# RobotCtrl_V2_Mother-board_Func.net
KiCad netlist of a schematic drawn in Altium Designer
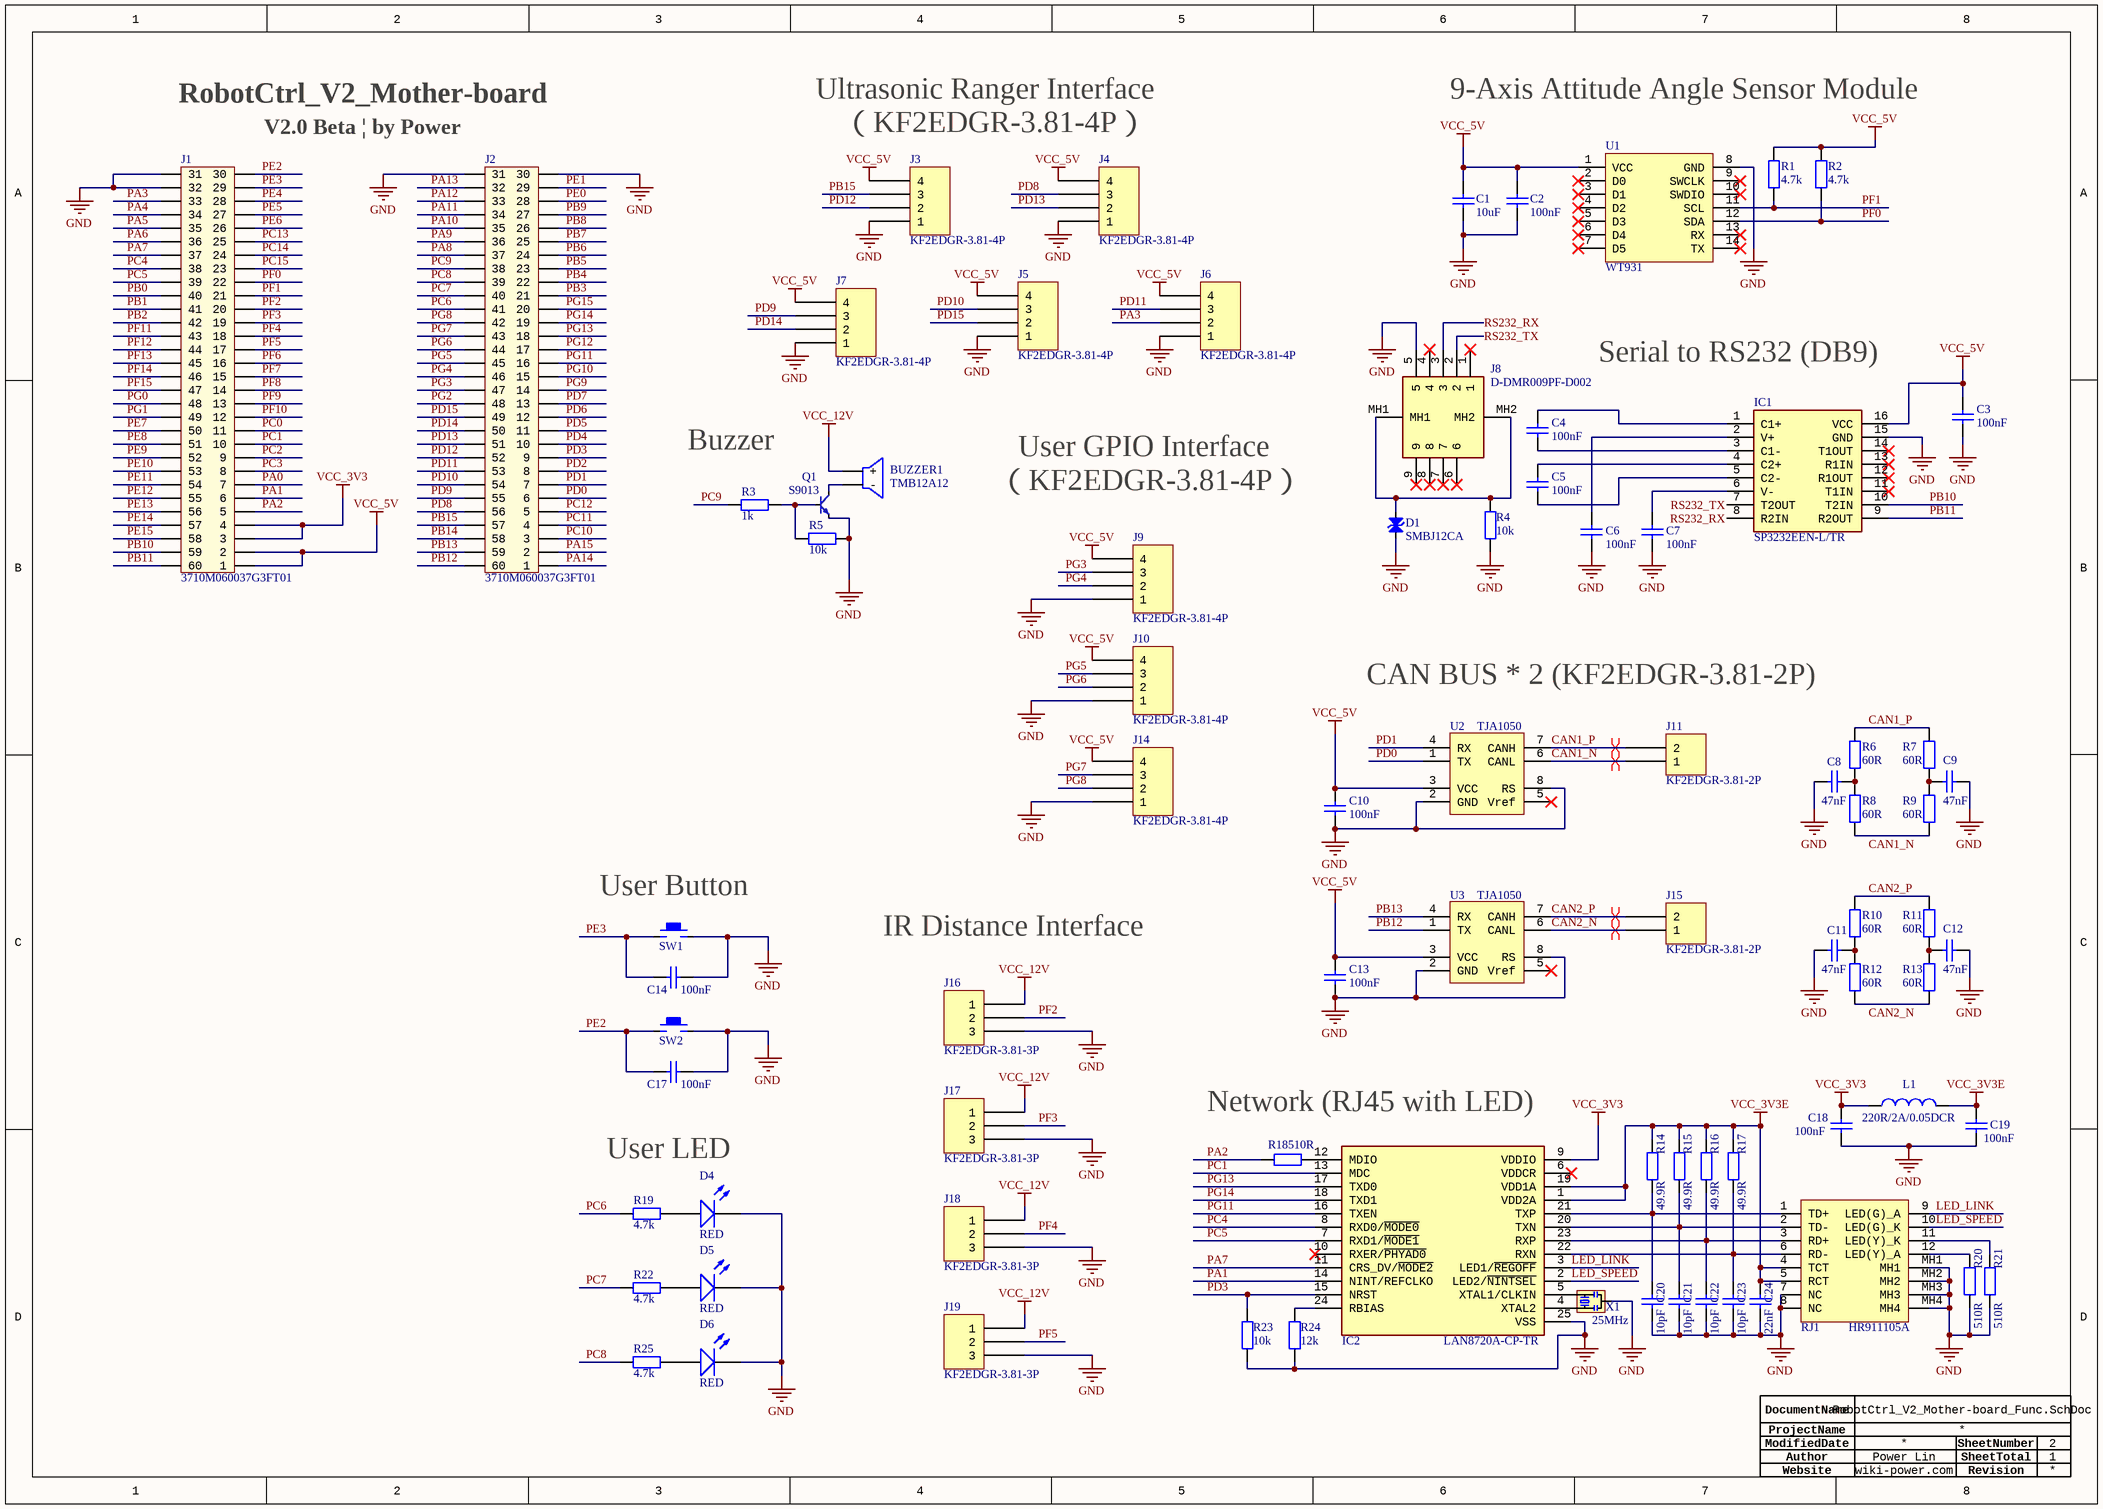
[diagram p0: RobotCtrl_V2_Mother-board_Func.SchDoc]

(export (version "E")
  (design (tool "Eeschema 10.0.6"))
  (components
    (comp (ref "BUZZER1")
      (value "TMB12A12")
      (footprint "DIP,P=7.6mm")
      (description "TMB12A12 有源蜂鸣器")
      (libsource (lib "Power_Lib_Altium") (part "BUZZER"))
    )
    (comp (ref "C1")
      (value "10uF")
      (footprint "CAP-0603")
      (description "贴片电容")
      (libsource (lib "Power_Lib_Altium") (part "CAP"))
    )
    (comp (ref "C2")
      (value "100nF")
      (footprint "CAP-0603")
      (description "贴片电容")
      (libsource (lib "Power_Lib_Altium") (part "CAP"))
    )
    (comp (ref "C3")
      (value "100nF")
      (footprint "CAP-0603")
      (description "贴片电容")
      (libsource (lib "Power_Lib_Altium") (part "CAP"))
    )
    (comp (ref "C4")
      (value "100nF")
      (footprint "CAP-0603")
      (description "贴片电容")
      (libsource (lib "Power_Lib_Altium") (part "CAP"))
    )
    (comp (ref "C5")
      (value "100nF")
      (footprint "CAP-0603")
      (description "贴片电容")
      (libsource (lib "Power_Lib_Altium") (part "CAP"))
    )
    (comp (ref "C6")
      (value "100nF")
      (footprint "CAP-0603")
      (description "贴片电容")
      (libsource (lib "Power_Lib_Altium") (part "CAP"))
    )
    (comp (ref "C7")
      (value "100nF")
      (footprint "CAP-0603")
      (description "贴片电容")
      (libsource (lib "Power_Lib_Altium") (part "CAP"))
    )
    (comp (ref "C8")
      (value "47nF")
      (footprint "CAP-0603")
      (description "贴片电容")
      (libsource (lib "Power_Lib_Altium") (part "CAP"))
    )
    (comp (ref "C9")
      (value "47nF")
      (footprint "CAP-0603")
      (description "贴片电容")
      (libsource (lib "Power_Lib_Altium") (part "CAP"))
    )
    (comp (ref "C10")
      (value "100nF")
      (footprint "CAP-0603")
      (description "贴片电容")
      (libsource (lib "Power_Lib_Altium") (part "CAP"))
    )
    (comp (ref "C11")
      (value "47nF")
      (footprint "CAP-0603")
      (description "贴片电容")
      (libsource (lib "Power_Lib_Altium") (part "CAP"))
    )
    (comp (ref "C12")
      (value "47nF")
      (footprint "CAP-0603")
      (description "贴片电容")
      (libsource (lib "Power_Lib_Altium") (part "CAP"))
    )
    (comp (ref "C13")
      (value "100nF")
      (footprint "CAP-0603")
      (description "贴片电容")
      (libsource (lib "Power_Lib_Altium") (part "CAP"))
    )
    (comp (ref "C14")
      (value "100nF")
      (footprint "CAP-0603")
      (description "贴片电容")
      (libsource (lib "Power_Lib_Altium") (part "CAP"))
    )
    (comp (ref "C17")
      (value "100nF")
      (footprint "CAP-0603")
      (description "贴片电容")
      (libsource (lib "Power_Lib_Altium") (part "CAP"))
    )
    (comp (ref "C18")
      (value "100nF")
      (footprint "CAP-0603")
      (description "贴片电容")
      (libsource (lib "Power_Lib_Altium") (part "CAP"))
    )
    (comp (ref "C19")
      (value "100nF")
      (footprint "CAP-0603")
      (description "贴片电容")
      (libsource (lib "Power_Lib_Altium") (part "CAP"))
    )
    (comp (ref "C20")
      (value "10pF")
      (footprint "CAP-0603")
      (description "贴片电容")
      (libsource (lib "Power_Lib_Altium") (part "CAP"))
    )
    (comp (ref "C21")
      (value "10pF")
      (footprint "CAP-0603")
      (description "贴片电容")
      (libsource (lib "Power_Lib_Altium") (part "CAP"))
    )
    (comp (ref "C22")
      (value "10pF")
      (footprint "CAP-0603")
      (description "贴片电容")
      (libsource (lib "Power_Lib_Altium") (part "CAP"))
    )
    (comp (ref "C23")
      (value "10pF")
      (footprint "CAP-0603")
      (description "贴片电容")
      (libsource (lib "Power_Lib_Altium") (part "CAP"))
    )
    (comp (ref "C24")
      (value "22nF")
      (footprint "CAP-0603")
      (description "贴片电容")
      (libsource (lib "Power_Lib_Altium") (part "CAP"))
    )
    (comp (ref "D1")
      (value "SMBJ12CA")
      (footprint "DO-214AA/SMB")
      (libsource (lib "Power_Lib_Altium") (part "TVS_C"))
    )
    (comp (ref "D4")
      (value "RED")
      (footprint "LED-0603")
      (description "发光二极管")
      (libsource (lib "Power_Lib_Altium") (part "LED"))
    )
    (comp (ref "D5")
      (value "RED")
      (footprint "LED-0603")
      (description "发光二极管")
      (libsource (lib "Power_Lib_Altium") (part "LED"))
    )
    (comp (ref "D6")
      (value "RED")
      (footprint "LED-0603")
      (description "发光二极管")
      (libsource (lib "Power_Lib_Altium") (part "LED"))
    )
    (comp (ref "IC1")
      (value "SP3232EEN-L/TR")
      (footprint "SOIC-16_150mil")
      (description "RS232 芯片")
      (fields (field (name "MOUSER PART NUMBER") "701-SP3232EEN-L/TR"))
      (libsource (lib "Power_Lib_Altium") (part "SP3232EEN"))
    )
    (comp (ref "IC2")
      (value "LAN8720A-CP-TR")
      (footprint "QFN-24-4x4")
      (description "Integrated Circuit")
      (fields (field (name "MOUSER PART NUMBER") "886-LAN8720A-CP-TR"))
      (libsource (lib "Power_Lib_Altium") (part "LAN8720A-CP-TR"))
    )
    (comp (ref "J1")
      (value "3710M060037G3FT01")
      (footprint "3710M060037G3FT01")
      (description "B2B Connector")
      (libsource (lib "Power_Lib_Altium") (part "3710M/F"))
    )
    (comp (ref "J2")
      (value "3710M060037G3FT01")
      (footprint "3710M060037G3FT01")
      (description "B2B Connector")
      (libsource (lib "Power_Lib_Altium") (part "3710M/F"))
    )
    (comp (ref "J3")
      (value "KF2EDGR-3.81-4P")
      (footprint "FCI 06-381-4PIN")
      (description "TERM BLOCK HDR 4POS 90DEG 3.81MM")
      (fields (field (name "PART NUMBER") "OQ0432510000G") (field (name "MANUFACTURER") "Amphenol Anytek"))
      (libsource (lib "Power_Lib_Altium") (part "KF2EDGR-3.81-4P"))
    )
    (comp (ref "J4")
      (value "KF2EDGR-3.81-4P")
      (footprint "FCI 06-381-4PIN")
      (description "TERM BLOCK HDR 4POS 90DEG 3.81MM")
      (fields (field (name "PART NUMBER") "OQ0432510000G") (field (name "MANUFACTURER") "Amphenol Anytek"))
      (libsource (lib "Power_Lib_Altium") (part "KF2EDGR-3.81-4P"))
    )
    (comp (ref "J5")
      (value "KF2EDGR-3.81-4P")
      (footprint "FCI 06-381-4PIN")
      (description "TERM BLOCK HDR 4POS 90DEG 3.81MM")
      (fields (field (name "PART NUMBER") "OQ0432510000G") (field (name "MANUFACTURER") "Amphenol Anytek"))
      (libsource (lib "Power_Lib_Altium") (part "KF2EDGR-3.81-4P"))
    )
    (comp (ref "J6")
      (value "KF2EDGR-3.81-4P")
      (footprint "FCI 06-381-4PIN")
      (description "TERM BLOCK HDR 4POS 90DEG 3.81MM")
      (fields (field (name "PART NUMBER") "OQ0432510000G") (field (name "MANUFACTURER") "Amphenol Anytek"))
      (libsource (lib "Power_Lib_Altium") (part "KF2EDGR-3.81-4P"))
    )
    (comp (ref "J7")
      (value "KF2EDGR-3.81-4P")
      (footprint "FCI 06-381-4PIN")
      (description "TERM BLOCK HDR 4POS 90DEG 3.81MM")
      (fields (field (name "PART NUMBER") "OQ0432510000G") (field (name "MANUFACTURER") "Amphenol Anytek"))
      (libsource (lib "Power_Lib_Altium") (part "KF2EDGR-3.81-4P"))
    )
    (comp (ref "J8")
      (value "D-DMR009PF-D002")
      (footprint "Through Hole,P=2.77mm")
      (description "D-Sub 连接器")
      (fields
        (field (name "MANUFACTURER_PART_NUMBER") "5747844-5")
        (field (name "MOUSER PART NUMBER") "571-5747844-5")
      )
      (libsource (lib "Power_Lib_Altium") (part "DB9"))
    )
    (comp (ref "J9")
      (value "KF2EDGR-3.81-4P")
      (footprint "FCI 06-381-4PIN")
      (description "TERM BLOCK HDR 4POS 90DEG 3.81MM")
      (fields (field (name "PART NUMBER") "OQ0432510000G") (field (name "MANUFACTURER") "Amphenol Anytek"))
      (libsource (lib "Power_Lib_Altium") (part "KF2EDGR-3.81-4P"))
    )
    (comp (ref "J10")
      (value "KF2EDGR-3.81-4P")
      (footprint "FCI 06-381-4PIN")
      (description "TERM BLOCK HDR 4POS 90DEG 3.81MM")
      (fields (field (name "PART NUMBER") "OQ0432510000G") (field (name "MANUFACTURER") "Amphenol Anytek"))
      (libsource (lib "Power_Lib_Altium") (part "KF2EDGR-3.81-4P"))
    )
    (comp (ref "J11")
      (value "KF2EDGR-3.81-2P")
      (footprint "FCI 06-381-2PIN")
      (description "TERM BLOCK HDR 2POS 90DEG 3.81MM")
      (fields (field (name "PART NUMBER") "OQ0232510000G") (field (name "MANUFACTURER") "Amphenol Anytek"))
      (libsource (lib "Power_Lib_Altium") (part "KF2EDGR-3.81-2P"))
    )
    (comp (ref "J14")
      (value "KF2EDGR-3.81-4P")
      (footprint "FCI 06-381-4PIN")
      (description "TERM BLOCK HDR 4POS 90DEG 3.81MM")
      (fields (field (name "PART NUMBER") "OQ0432510000G") (field (name "MANUFACTURER") "Amphenol Anytek"))
      (libsource (lib "Power_Lib_Altium") (part "KF2EDGR-3.81-4P"))
    )
    (comp (ref "J15")
      (value "KF2EDGR-3.81-2P")
      (footprint "FCI 06-381-2PIN")
      (description "TERM BLOCK HDR 2POS 90DEG 3.81MM")
      (fields (field (name "PART NUMBER") "OQ0232510000G") (field (name "MANUFACTURER") "Amphenol Anytek"))
      (libsource (lib "Power_Lib_Altium") (part "KF2EDGR-3.81-2P"))
    )
    (comp (ref "J16")
      (value "KF2EDGR-3.81-3P")
      (footprint "FCI 06-381-3PIN")
      (description "TERM BLOCK HDR 3POS 90DEG 3.81MM")
      (fields (field (name "MANUFACTURER") "Amphenol Anytek") (field (name "PART NUMBER") "OQ0332510000G"))
      (libsource (lib "Power_Lib_Altium") (part "KF2EDGR-3.81-3P"))
    )
    (comp (ref "J17")
      (value "KF2EDGR-3.81-3P")
      (footprint "FCI 06-381-3PIN")
      (description "TERM BLOCK HDR 3POS 90DEG 3.81MM")
      (fields (field (name "MANUFACTURER") "Amphenol Anytek") (field (name "PART NUMBER") "OQ0332510000G"))
      (libsource (lib "Power_Lib_Altium") (part "KF2EDGR-3.81-3P"))
    )
    (comp (ref "J18")
      (value "KF2EDGR-3.81-3P")
      (footprint "FCI 06-381-3PIN")
      (description "TERM BLOCK HDR 3POS 90DEG 3.81MM")
      (fields (field (name "MANUFACTURER") "Amphenol Anytek") (field (name "PART NUMBER") "OQ0332510000G"))
      (libsource (lib "Power_Lib_Altium") (part "KF2EDGR-3.81-3P"))
    )
    (comp (ref "J19")
      (value "KF2EDGR-3.81-3P")
      (footprint "FCI 06-381-3PIN")
      (description "TERM BLOCK HDR 3POS 90DEG 3.81MM")
      (fields (field (name "MANUFACTURER") "Amphenol Anytek") (field (name "PART NUMBER") "OQ0332510000G"))
      (libsource (lib "Power_Lib_Altium") (part "KF2EDGR-3.81-3P"))
    )
    (comp (ref "L1")
      (value "220R/2A/0.05DCR")
      (footprint "L-0603")
      (description "BLM18KG221SN1D")
      (libsource (lib "Power_Lib_Altium") (part "BEAD"))
    )
    (comp (ref "Q1")
      (value "S9013")
      (footprint "SOT-23-3")
      (libsource (lib "Power_Lib_Altium") (part "BJT_NPN"))
    )
    (comp (ref "R1")
      (value "4.7k")
      (footprint "R-0603")
      (description "贴片电阻")
      (libsource (lib "") (part "RES_3"))
    )
    (comp (ref "R2")
      (value "4.7k")
      (footprint "R-0603")
      (description "贴片电阻")
      (libsource (lib "") (part "RES_3"))
    )
    (comp (ref "R3")
      (value "1k")
      (footprint "R-0603")
      (description "贴片电阻")
      (libsource (lib "") (part "RES_2"))
    )
    (comp (ref "R4")
      (value "10k")
      (footprint "R-0603")
      (description "贴片电阻")
      (libsource (lib "") (part "RES_3"))
    )
    (comp (ref "R5")
      (value "10k")
      (footprint "R-0603")
      (description "贴片电阻")
      (libsource (lib "Power_Lib_Altium") (part "RES"))
    )
    (comp (ref "R6")
      (value "60R")
      (footprint "R-0603")
      (description "贴片电阻")
      (libsource (lib "") (part "RES_1"))
    )
    (comp (ref "R7")
      (value "60R")
      (footprint "R-0603")
      (description "贴片电阻")
      (libsource (lib "") (part "RES_3"))
    )
    (comp (ref "R8")
      (value "60R")
      (footprint "R-0603")
      (description "贴片电阻")
      (libsource (lib "") (part "RES_1"))
    )
    (comp (ref "R9")
      (value "60R")
      (footprint "R-0603")
      (description "贴片电阻")
      (libsource (lib "") (part "RES_3"))
    )
    (comp (ref "R10")
      (value "60R")
      (footprint "R-0603")
      (description "贴片电阻")
      (libsource (lib "") (part "RES_1"))
    )
    (comp (ref "R11")
      (value "60R")
      (footprint "R-0603")
      (description "贴片电阻")
      (libsource (lib "") (part "RES_3"))
    )
    (comp (ref "R12")
      (value "60R")
      (footprint "R-0603")
      (description "贴片电阻")
      (libsource (lib "") (part "RES_1"))
    )
    (comp (ref "R13")
      (value "60R")
      (footprint "R-0603")
      (description "贴片电阻")
      (libsource (lib "") (part "RES_3"))
    )
    (comp (ref "R14")
      (value "49.9R")
      (footprint "R-0603")
      (description "贴片电阻")
      (libsource (lib "") (part "RES_3"))
    )
    (comp (ref "R15")
      (value "49.9R")
      (footprint "R-0603")
      (description "贴片电阻")
      (libsource (lib "") (part "RES_3"))
    )
    (comp (ref "R16")
      (value "49.9R")
      (footprint "R-0603")
      (description "贴片电阻")
      (libsource (lib "") (part "RES_3"))
    )
    (comp (ref "R17")
      (value "49.9R")
      (footprint "R-0603")
      (description "贴片电阻")
      (libsource (lib "") (part "RES_3"))
    )
    (comp (ref "R18")
      (value "510R")
      (footprint "R-0603")
      (description "贴片电阻")
      (libsource (lib "Power_Lib_Altium") (part "RES"))
    )
    (comp (ref "R19")
      (value "4.7k")
      (footprint "R-0603")
      (description "贴片电阻")
      (libsource (lib "Power_Lib_Altium") (part "RES"))
    )
    (comp (ref "R20")
      (value "510R")
      (footprint "R-0603")
      (description "贴片电阻")
      (libsource (lib "") (part "RES_3"))
    )
    (comp (ref "R21")
      (value "510R")
      (footprint "R-0603")
      (description "贴片电阻")
      (libsource (lib "") (part "RES_3"))
    )
    (comp (ref "R22")
      (value "4.7k")
      (footprint "R-0603")
      (description "贴片电阻")
      (libsource (lib "Power_Lib_Altium") (part "RES"))
    )
    (comp (ref "R23")
      (value "10k")
      (footprint "R-0603")
      (description "贴片电阻")
      (libsource (lib "") (part "RES_1"))
    )
    (comp (ref "R24")
      (value "12k")
      (footprint "R-0603")
      (description "贴片电阻")
      (libsource (lib "") (part "RES_1"))
    )
    (comp (ref "R25")
      (value "4.7k")
      (footprint "R-0603")
      (description "贴片电阻")
      (libsource (lib "Power_Lib_Altium") (part "RES"))
    )
    (comp (ref "RJ1")
      (value "HR911105A")
      (footprint "HR911105A")
      (libsource (lib "Power_Lib_Altium") (part "RJ45_LED"))
    )
    (comp (ref "SW1")
      (value "KEY")
      (footprint "KEY-4P-4.2*3.4*2.5")
      (description "按键开关")
      (libsource (lib "Power_Lib_Altium") (part "KEY"))
    )
    (comp (ref "SW2")
      (value "KEY")
      (footprint "KEY-4P-4.2*3.4*2.5")
      (description "按键开关")
      (libsource (lib "Power_Lib_Altium") (part "KEY"))
    )
    (comp (ref "U1")
      (value "WT931")
      (footprint "WT931")
      (description "陀螺仪模组")
      (libsource (lib "Power_Lib_Altium") (part "WT931"))
    )
    (comp (ref "U2")
      (value "TJA1050")
      (footprint "SOIC_8")
      (description "CAN 控制器（5V）")
      (libsource (lib "Power_Lib_Altium") (part "TJA1050"))
    )
    (comp (ref "U3")
      (value "TJA1050")
      (footprint "SOIC_8")
      (description "CAN 控制器（5V）")
      (libsource (lib "Power_Lib_Altium") (part "TJA1050"))
    )
    (comp (ref "X1")
      (value "25MHz")
      (footprint "SMD3213-3P")
      (description "CSTCE25M00G51-R0")
      (libsource (lib "Power_Lib_Altium") (part "XTAL"))
    )
  )
  (nets
    (net (code "1") (name "/CAN1_N") (class "Default")
      (node (ref "J11") (pin "1") (pinfunction "1_1") (pintype "passive"))
      (node (ref "R8") (pin "2") (pinfunction "2_2") (pintype "passive"))
      (node (ref "R9") (pin "1") (pinfunction "1_1") (pintype "passive"))
      (node (ref "U2") (pin "6") (pinfunction "CANL_6") (pintype "passive"))
    )
    (net (code "2") (name "/CAN1_P") (class "Default")
      (node (ref "J11") (pin "2") (pinfunction "2_2") (pintype "passive"))
      (node (ref "R6") (pin "1") (pinfunction "1_1") (pintype "passive"))
      (node (ref "R7") (pin "2") (pinfunction "2_2") (pintype "passive"))
      (node (ref "U2") (pin "7") (pinfunction "CANH_7") (pintype "passive"))
    )
    (net (code "3") (name "/CAN2_N") (class "Default")
      (node (ref "J15") (pin "1") (pinfunction "1_1") (pintype "passive"))
      (node (ref "R12") (pin "2") (pinfunction "2_2") (pintype "passive"))
      (node (ref "R13") (pin "1") (pinfunction "1_1") (pintype "passive"))
      (node (ref "U3") (pin "6") (pinfunction "CANL_6") (pintype "passive"))
    )
    (net (code "4") (name "/CAN2_P") (class "Default")
      (node (ref "J15") (pin "2") (pinfunction "2_2") (pintype "passive"))
      (node (ref "R10") (pin "1") (pinfunction "1_1") (pintype "passive"))
      (node (ref "R11") (pin "2") (pinfunction "2_2") (pintype "passive"))
      (node (ref "U3") (pin "7") (pinfunction "CANH_7") (pintype "passive"))
    )
    (net (code "5") (name "/LED_LINK") (class "Default")
      (node (ref "IC2") (pin "3") (pinfunction "LED1/~{REGOFF}_3") (pintype "passive"))
      (node (ref "RJ1") (pin "9") (pinfunction "LED(G)_A_9") (pintype "passive"))
    )
    (net (code "6") (name "/LED_SPEED") (class "Default")
      (node (ref "IC2") (pin "2") (pinfunction "LED2/~{NINTSEL}_2") (pintype "passive"))
      (node (ref "RJ1") (pin "10") (pinfunction "LED(G)_K_10") (pintype "passive"))
    )
    (net (code "7") (name "/PA0") (class "Default")
      (node (ref "J1") (pin "7") (pinfunction "7_7") (pintype "passive"))
    )
    (net (code "8") (name "/PA1") (class "Default")
      (node (ref "IC2") (pin "14") (pinfunction "NINT/REFCLKO_14") (pintype "passive"))
      (node (ref "J1") (pin "6") (pinfunction "6_6") (pintype "passive"))
    )
    (net (code "9") (name "/PA2") (class "Default")
      (node (ref "J1") (pin "5") (pinfunction "5_5") (pintype "passive"))
      (node (ref "R18") (pin "2") (pinfunction "2_2") (pintype "passive"))
    )
    (net (code "10") (name "/PA3") (class "Default")
      (node (ref "J1") (pin "33") (pinfunction "33_33") (pintype "passive"))
      (node (ref "J6") (pin "2") (pinfunction "2_2") (pintype "passive"))
    )
    (net (code "11") (name "/PA4") (class "Default")
      (node (ref "J1") (pin "34") (pinfunction "34_34") (pintype "passive"))
    )
    (net (code "12") (name "/PA5") (class "Default")
      (node (ref "J1") (pin "35") (pinfunction "35_35") (pintype "passive"))
    )
    (net (code "13") (name "/PA6") (class "Default")
      (node (ref "J1") (pin "36") (pinfunction "36_36") (pintype "passive"))
    )
    (net (code "14") (name "/PA7") (class "Default")
      (node (ref "IC2") (pin "11") (pinfunction "CRS_DV/~{MODE2}_11") (pintype "passive"))
      (node (ref "J1") (pin "37") (pinfunction "37_37") (pintype "passive"))
    )
    (net (code "15") (name "/PA8") (class "Default")
      (node (ref "J2") (pin "37") (pinfunction "37_37") (pintype "passive"))
    )
    (net (code "16") (name "/PA9") (class "Default")
      (node (ref "J2") (pin "36") (pinfunction "36_36") (pintype "passive"))
    )
    (net (code "17") (name "/PA10") (class "Default")
      (node (ref "J2") (pin "35") (pinfunction "35_35") (pintype "passive"))
    )
    (net (code "18") (name "/PA11") (class "Default")
      (node (ref "J2") (pin "34") (pinfunction "34_34") (pintype "passive"))
    )
    (net (code "19") (name "/PA12") (class "Default")
      (node (ref "J2") (pin "33") (pinfunction "33_33") (pintype "passive"))
    )
    (net (code "20") (name "/PA13") (class "Default")
      (node (ref "J2") (pin "32") (pinfunction "32_32") (pintype "passive"))
    )
    (net (code "21") (name "/PA14") (class "Default")
      (node (ref "J2") (pin "1") (pinfunction "1_1") (pintype "passive"))
    )
    (net (code "22") (name "/PA15") (class "Default")
      (node (ref "J2") (pin "2") (pinfunction "2_2") (pintype "passive"))
    )
    (net (code "23") (name "/PB0") (class "Default")
      (node (ref "J1") (pin "40") (pinfunction "40_40") (pintype "passive"))
    )
    (net (code "24") (name "/PB1") (class "Default")
      (node (ref "J1") (pin "41") (pinfunction "41_41") (pintype "passive"))
    )
    (net (code "25") (name "/PB2") (class "Default")
      (node (ref "J1") (pin "42") (pinfunction "42_42") (pintype "passive"))
    )
    (net (code "26") (name "/PB3") (class "Default")
      (node (ref "J2") (pin "21") (pinfunction "21_21") (pintype "passive"))
    )
    (net (code "27") (name "/PB4") (class "Default")
      (node (ref "J2") (pin "22") (pinfunction "22_22") (pintype "passive"))
    )
    (net (code "28") (name "/PB5") (class "Default")
      (node (ref "J2") (pin "23") (pinfunction "23_23") (pintype "passive"))
    )
    (net (code "29") (name "/PB6") (class "Default")
      (node (ref "J2") (pin "24") (pinfunction "24_24") (pintype "passive"))
    )
    (net (code "30") (name "/PB7") (class "Default")
      (node (ref "J2") (pin "25") (pinfunction "25_25") (pintype "passive"))
    )
    (net (code "31") (name "/PB8") (class "Default")
      (node (ref "J2") (pin "26") (pinfunction "26_26") (pintype "passive"))
    )
    (net (code "32") (name "/PB9") (class "Default")
      (node (ref "J2") (pin "27") (pinfunction "27_27") (pintype "passive"))
    )
    (net (code "33") (name "/PB10") (class "Default")
      (node (ref "IC1") (pin "10") (pinfunction "T2IN_10") (pintype "passive"))
      (node (ref "J1") (pin "59") (pinfunction "59_59") (pintype "passive"))
    )
    (net (code "34") (name "/PB11") (class "Default")
      (node (ref "IC1") (pin "9") (pinfunction "R2OUT_9") (pintype "passive"))
      (node (ref "J1") (pin "60") (pinfunction "60_60") (pintype "passive"))
    )
    (net (code "35") (name "/PB12") (class "Default")
      (node (ref "J2") (pin "60") (pinfunction "60_60") (pintype "passive"))
      (node (ref "U3") (pin "1") (pinfunction "TX_1") (pintype "passive"))
    )
    (net (code "36") (name "/PB13") (class "Default")
      (node (ref "J2") (pin "59") (pinfunction "59_59") (pintype "passive"))
      (node (ref "U3") (pin "4") (pinfunction "RX_4") (pintype "passive"))
    )
    (net (code "37") (name "/PB14") (class "Default")
      (node (ref "J2") (pin "58") (pinfunction "58_58") (pintype "passive"))
    )
    (net (code "38") (name "/PB15") (class "Default")
      (node (ref "J2") (pin "57") (pinfunction "57_57") (pintype "passive"))
      (node (ref "J3") (pin "3") (pinfunction "3_3") (pintype "passive"))
    )
    (net (code "39") (name "/PC0") (class "Default")
      (node (ref "J1") (pin "11") (pinfunction "11_11") (pintype "passive"))
    )
    (net (code "40") (name "/PC1") (class "Default")
      (node (ref "IC2") (pin "13") (pinfunction "MDC_13") (pintype "passive"))
      (node (ref "J1") (pin "10") (pinfunction "10_10") (pintype "passive"))
    )
    (net (code "41") (name "/PC2") (class "Default")
      (node (ref "J1") (pin "9") (pinfunction "9_9") (pintype "passive"))
    )
    (net (code "42") (name "/PC3") (class "Default")
      (node (ref "J1") (pin "8") (pinfunction "8_8") (pintype "passive"))
    )
    (net (code "43") (name "/PC4") (class "Default")
      (node (ref "IC2") (pin "8") (pinfunction "RXD0/~{MODE0}_8") (pintype "passive"))
      (node (ref "J1") (pin "38") (pinfunction "38_38") (pintype "passive"))
    )
    (net (code "44") (name "/PC5") (class "Default")
      (node (ref "IC2") (pin "7") (pinfunction "RXD1/~{MODE1}_7") (pintype "passive"))
      (node (ref "J1") (pin "39") (pinfunction "39_39") (pintype "passive"))
    )
    (net (code "45") (name "/PC6") (class "Default")
      (node (ref "J2") (pin "41") (pinfunction "41_41") (pintype "passive"))
      (node (ref "R19") (pin "2") (pinfunction "2_2") (pintype "passive"))
    )
    (net (code "46") (name "/PC7") (class "Default")
      (node (ref "J2") (pin "40") (pinfunction "40_40") (pintype "passive"))
      (node (ref "R22") (pin "2") (pinfunction "2_2") (pintype "passive"))
    )
    (net (code "47") (name "/PC8") (class "Default")
      (node (ref "J2") (pin "39") (pinfunction "39_39") (pintype "passive"))
      (node (ref "R25") (pin "2") (pinfunction "2_2") (pintype "passive"))
    )
    (net (code "48") (name "/PC9") (class "Default")
      (node (ref "J2") (pin "38") (pinfunction "38_38") (pintype "passive"))
      (node (ref "R3") (pin "1") (pinfunction "1_1") (pintype "passive"))
    )
    (net (code "49") (name "/PC10") (class "Default")
      (node (ref "J2") (pin "3") (pinfunction "3_3") (pintype "passive"))
    )
    (net (code "50") (name "/PC11") (class "Default")
      (node (ref "J2") (pin "4") (pinfunction "4_4") (pintype "passive"))
    )
    (net (code "51") (name "/PC12") (class "Default")
      (node (ref "J2") (pin "5") (pinfunction "5_5") (pintype "passive"))
    )
    (net (code "52") (name "/PC13") (class "Default")
      (node (ref "J1") (pin "25") (pinfunction "25_25") (pintype "passive"))
    )
    (net (code "53") (name "/PC14") (class "Default")
      (node (ref "J1") (pin "24") (pinfunction "24_24") (pintype "passive"))
    )
    (net (code "54") (name "/PC15") (class "Default")
      (node (ref "J1") (pin "23") (pinfunction "23_23") (pintype "passive"))
    )
    (net (code "55") (name "/PD0") (class "Default")
      (node (ref "J2") (pin "6") (pinfunction "6_6") (pintype "passive"))
      (node (ref "U2") (pin "1") (pinfunction "TX_1") (pintype "passive"))
    )
    (net (code "56") (name "/PD1") (class "Default")
      (node (ref "J2") (pin "7") (pinfunction "7_7") (pintype "passive"))
      (node (ref "U2") (pin "4") (pinfunction "RX_4") (pintype "passive"))
    )
    (net (code "57") (name "/PD2") (class "Default")
      (node (ref "J2") (pin "8") (pinfunction "8_8") (pintype "passive"))
    )
    (net (code "58") (name "/PD3") (class "Default")
      (node (ref "IC2") (pin "15") (pinfunction "NRST_15") (pintype "passive"))
      (node (ref "J2") (pin "9") (pinfunction "9_9") (pintype "passive"))
      (node (ref "R23") (pin "1") (pinfunction "1_1") (pintype "passive"))
    )
    (net (code "59") (name "/PD4") (class "Default")
      (node (ref "J2") (pin "10") (pinfunction "10_10") (pintype "passive"))
    )
    (net (code "60") (name "/PD5") (class "Default")
      (node (ref "J2") (pin "11") (pinfunction "11_11") (pintype "passive"))
    )
    (net (code "61") (name "/PD6") (class "Default")
      (node (ref "J2") (pin "12") (pinfunction "12_12") (pintype "passive"))
    )
    (net (code "62") (name "/PD7") (class "Default")
      (node (ref "J2") (pin "13") (pinfunction "13_13") (pintype "passive"))
    )
    (net (code "63") (name "/PD8") (class "Default")
      (node (ref "J2") (pin "56") (pinfunction "56_56") (pintype "passive"))
      (node (ref "J4") (pin "3") (pinfunction "3_3") (pintype "passive"))
    )
    (net (code "64") (name "/PD9") (class "Default")
      (node (ref "J2") (pin "55") (pinfunction "55_55") (pintype "passive"))
      (node (ref "J7") (pin "3") (pinfunction "3_3") (pintype "passive"))
    )
    (net (code "65") (name "/PD10") (class "Default")
      (node (ref "J2") (pin "54") (pinfunction "54_54") (pintype "passive"))
      (node (ref "J5") (pin "3") (pinfunction "3_3") (pintype "passive"))
    )
    (net (code "66") (name "/PD11") (class "Default")
      (node (ref "J2") (pin "53") (pinfunction "53_53") (pintype "passive"))
      (node (ref "J6") (pin "3") (pinfunction "3_3") (pintype "passive"))
    )
    (net (code "67") (name "/PD12") (class "Default")
      (node (ref "J2") (pin "52") (pinfunction "52_52") (pintype "passive"))
      (node (ref "J3") (pin "2") (pinfunction "2_2") (pintype "passive"))
    )
    (net (code "68") (name "/PD13") (class "Default")
      (node (ref "J2") (pin "51") (pinfunction "51_51") (pintype "passive"))
      (node (ref "J4") (pin "2") (pinfunction "2_2") (pintype "passive"))
    )
    (net (code "69") (name "/PD14") (class "Default")
      (node (ref "J2") (pin "50") (pinfunction "50_50") (pintype "passive"))
      (node (ref "J7") (pin "2") (pinfunction "2_2") (pintype "passive"))
    )
    (net (code "70") (name "/PD15") (class "Default")
      (node (ref "J2") (pin "49") (pinfunction "49_49") (pintype "passive"))
      (node (ref "J5") (pin "2") (pinfunction "2_2") (pintype "passive"))
    )
    (net (code "71") (name "/PE0") (class "Default")
      (node (ref "J2") (pin "28") (pinfunction "28_28") (pintype "passive"))
    )
    (net (code "72") (name "/PE1") (class "Default")
      (node (ref "J2") (pin "29") (pinfunction "29_29") (pintype "passive"))
    )
    (net (code "73") (name "/PE2") (class "Default")
      (node (ref "C17") (pin "2") (pinfunction "2_2") (pintype "passive"))
      (node (ref "J1") (pin "30") (pinfunction "30_30") (pintype "passive"))
      (node (ref "SW2") (pin "1") (pinfunction "1_1") (pintype "passive"))
    )
    (net (code "74") (name "/PE3") (class "Default")
      (node (ref "C14") (pin "2") (pinfunction "2_2") (pintype "passive"))
      (node (ref "J1") (pin "29") (pinfunction "29_29") (pintype "passive"))
      (node (ref "SW1") (pin "1") (pinfunction "1_1") (pintype "passive"))
    )
    (net (code "75") (name "/PE4") (class "Default")
      (node (ref "J1") (pin "28") (pinfunction "28_28") (pintype "passive"))
    )
    (net (code "76") (name "/PE5") (class "Default")
      (node (ref "J1") (pin "27") (pinfunction "27_27") (pintype "passive"))
    )
    (net (code "77") (name "/PE6") (class "Default")
      (node (ref "J1") (pin "26") (pinfunction "26_26") (pintype "passive"))
    )
    (net (code "78") (name "/PE7") (class "Default")
      (node (ref "J1") (pin "50") (pinfunction "50_50") (pintype "passive"))
    )
    (net (code "79") (name "/PE8") (class "Default")
      (node (ref "J1") (pin "51") (pinfunction "51_51") (pintype "passive"))
    )
    (net (code "80") (name "/PE9") (class "Default")
      (node (ref "J1") (pin "52") (pinfunction "52_52") (pintype "passive"))
    )
    (net (code "81") (name "/PE10") (class "Default")
      (node (ref "J1") (pin "53") (pinfunction "53_53") (pintype "passive"))
    )
    (net (code "82") (name "/PE11") (class "Default")
      (node (ref "J1") (pin "54") (pinfunction "54_54") (pintype "passive"))
    )
    (net (code "83") (name "/PE12") (class "Default")
      (node (ref "J1") (pin "55") (pinfunction "55_55") (pintype "passive"))
    )
    (net (code "84") (name "/PE13") (class "Default")
      (node (ref "J1") (pin "56") (pinfunction "56_56") (pintype "passive"))
    )
    (net (code "85") (name "/PE14") (class "Default")
      (node (ref "J1") (pin "57") (pinfunction "57_57") (pintype "passive"))
    )
    (net (code "86") (name "/PE15") (class "Default")
      (node (ref "J1") (pin "58") (pinfunction "58_58") (pintype "passive"))
    )
    (net (code "87") (name "/PF0") (class "Default")
      (node (ref "J1") (pin "22") (pinfunction "22_22") (pintype "passive"))
      (node (ref "R2") (pin "1") (pinfunction "1_1") (pintype "passive"))
      (node (ref "U1") (pin "12") (pinfunction "SDA_12") (pintype "passive"))
    )
    (net (code "88") (name "/PF1") (class "Default")
      (node (ref "J1") (pin "21") (pinfunction "21_21") (pintype "passive"))
      (node (ref "R1") (pin "1") (pinfunction "1_1") (pintype "passive"))
      (node (ref "U1") (pin "11") (pinfunction "SCL_11") (pintype "passive"))
    )
    (net (code "89") (name "/PF2") (class "Default")
      (node (ref "J1") (pin "20") (pinfunction "20_20") (pintype "passive"))
      (node (ref "J16") (pin "2") (pinfunction "2_2") (pintype "passive"))
    )
    (net (code "90") (name "/PF3") (class "Default")
      (node (ref "J1") (pin "19") (pinfunction "19_19") (pintype "passive"))
      (node (ref "J17") (pin "2") (pinfunction "2_2") (pintype "passive"))
    )
    (net (code "91") (name "/PF4") (class "Default")
      (node (ref "J1") (pin "18") (pinfunction "18_18") (pintype "passive"))
      (node (ref "J18") (pin "2") (pinfunction "2_2") (pintype "passive"))
    )
    (net (code "92") (name "/PF5") (class "Default")
      (node (ref "J1") (pin "17") (pinfunction "17_17") (pintype "passive"))
      (node (ref "J19") (pin "2") (pinfunction "2_2") (pintype "passive"))
    )
    (net (code "93") (name "/PF6") (class "Default")
      (node (ref "J1") (pin "16") (pinfunction "16_16") (pintype "passive"))
    )
    (net (code "94") (name "/PF7") (class "Default")
      (node (ref "J1") (pin "15") (pinfunction "15_15") (pintype "passive"))
    )
    (net (code "95") (name "/PF8") (class "Default")
      (node (ref "J1") (pin "14") (pinfunction "14_14") (pintype "passive"))
    )
    (net (code "96") (name "/PF9") (class "Default")
      (node (ref "J1") (pin "13") (pinfunction "13_13") (pintype "passive"))
    )
    (net (code "97") (name "/PF10") (class "Default")
      (node (ref "J1") (pin "12") (pinfunction "12_12") (pintype "passive"))
    )
    (net (code "98") (name "/PF11") (class "Default")
      (node (ref "J1") (pin "43") (pinfunction "43_43") (pintype "passive"))
    )
    (net (code "99") (name "/PF12") (class "Default")
      (node (ref "J1") (pin "44") (pinfunction "44_44") (pintype "passive"))
    )
    (net (code "100") (name "/PF13") (class "Default")
      (node (ref "J1") (pin "45") (pinfunction "45_45") (pintype "passive"))
    )
    (net (code "101") (name "/PF14") (class "Default")
      (node (ref "J1") (pin "46") (pinfunction "46_46") (pintype "passive"))
    )
    (net (code "102") (name "/PF15") (class "Default")
      (node (ref "J1") (pin "47") (pinfunction "47_47") (pintype "passive"))
    )
    (net (code "103") (name "/PG0") (class "Default")
      (node (ref "J1") (pin "48") (pinfunction "48_48") (pintype "passive"))
    )
    (net (code "104") (name "/PG1") (class "Default")
      (node (ref "J1") (pin "49") (pinfunction "49_49") (pintype "passive"))
    )
    (net (code "105") (name "/PG2") (class "Default")
      (node (ref "J2") (pin "48") (pinfunction "48_48") (pintype "passive"))
    )
    (net (code "106") (name "/PG3") (class "Default")
      (node (ref "J2") (pin "47") (pinfunction "47_47") (pintype "passive"))
      (node (ref "J9") (pin "3") (pinfunction "3_3") (pintype "passive"))
    )
    (net (code "107") (name "/PG4") (class "Default")
      (node (ref "J2") (pin "46") (pinfunction "46_46") (pintype "passive"))
      (node (ref "J9") (pin "2") (pinfunction "2_2") (pintype "passive"))
    )
    (net (code "108") (name "/PG5") (class "Default")
      (node (ref "J10") (pin "3") (pinfunction "3_3") (pintype "passive"))
      (node (ref "J2") (pin "45") (pinfunction "45_45") (pintype "passive"))
    )
    (net (code "109") (name "/PG6") (class "Default")
      (node (ref "J10") (pin "2") (pinfunction "2_2") (pintype "passive"))
      (node (ref "J2") (pin "44") (pinfunction "44_44") (pintype "passive"))
    )
    (net (code "110") (name "/PG7") (class "Default")
      (node (ref "J14") (pin "3") (pinfunction "3_3") (pintype "passive"))
      (node (ref "J2") (pin "43") (pinfunction "43_43") (pintype "passive"))
    )
    (net (code "111") (name "/PG8") (class "Default")
      (node (ref "J14") (pin "2") (pinfunction "2_2") (pintype "passive"))
      (node (ref "J2") (pin "42") (pinfunction "42_42") (pintype "passive"))
    )
    (net (code "112") (name "/PG9") (class "Default")
      (node (ref "J2") (pin "14") (pinfunction "14_14") (pintype "passive"))
    )
    (net (code "113") (name "/PG10") (class "Default")
      (node (ref "J2") (pin "15") (pinfunction "15_15") (pintype "passive"))
    )
    (net (code "114") (name "/PG11") (class "Default")
      (node (ref "IC2") (pin "16") (pinfunction "TXEN_16") (pintype "passive"))
      (node (ref "J2") (pin "16") (pinfunction "16_16") (pintype "passive"))
    )
    (net (code "115") (name "/PG12") (class "Default")
      (node (ref "J2") (pin "17") (pinfunction "17_17") (pintype "passive"))
    )
    (net (code "116") (name "/PG13") (class "Default")
      (node (ref "IC2") (pin "17") (pinfunction "TXD0_17") (pintype "passive"))
      (node (ref "J2") (pin "18") (pinfunction "18_18") (pintype "passive"))
    )
    (net (code "117") (name "/PG14") (class "Default")
      (node (ref "IC2") (pin "18") (pinfunction "TXD1_18") (pintype "passive"))
      (node (ref "J2") (pin "19") (pinfunction "19_19") (pintype "passive"))
    )
    (net (code "118") (name "/PG15") (class "Default")
      (node (ref "J2") (pin "20") (pinfunction "20_20") (pintype "passive"))
    )
    (net (code "119") (name "/RS232_RX") (class "Default")
      (node (ref "IC1") (pin "8") (pinfunction "R2IN_8") (pintype "passive"))
      (node (ref "J8") (pin "3") (pinfunction "3_3") (pintype "passive"))
    )
    (net (code "120") (name "/RS232_TX") (class "Default")
      (node (ref "IC1") (pin "7") (pinfunction "T2OUT_7") (pintype "passive"))
      (node (ref "J8") (pin "2") (pinfunction "2_2") (pintype "passive"))
    )
    (net (code "121") (name "GND") (class "Default")
      (node (ref "C1") (pin "2") (pinfunction "2_2") (pintype "passive"))
      (node (ref "C10") (pin "1") (pinfunction "1_1") (pintype "passive"))
      (node (ref "C11") (pin "2") (pinfunction "2_2") (pintype "passive"))
      (node (ref "C12") (pin "2") (pinfunction "2_2") (pintype "passive"))
      (node (ref "C13") (pin "1") (pinfunction "1_1") (pintype "passive"))
      (node (ref "C14") (pin "1") (pinfunction "1_1") (pintype "passive"))
      (node (ref "C17") (pin "1") (pinfunction "1_1") (pintype "passive"))
      (node (ref "C18") (pin "1") (pinfunction "1_1") (pintype "passive"))
      (node (ref "C19") (pin "1") (pinfunction "1_1") (pintype "passive"))
      (node (ref "C2") (pin "2") (pinfunction "2_2") (pintype "passive"))
      (node (ref "C20") (pin "1") (pinfunction "1_1") (pintype "passive"))
      (node (ref "C21") (pin "1") (pinfunction "1_1") (pintype "passive"))
      (node (ref "C22") (pin "1") (pinfunction "1_1") (pintype "passive"))
      (node (ref "C23") (pin "1") (pinfunction "1_1") (pintype "passive"))
      (node (ref "C24") (pin "1") (pinfunction "1_1") (pintype "passive"))
      (node (ref "C3") (pin "1") (pinfunction "1_1") (pintype "passive"))
      (node (ref "C6") (pin "1") (pinfunction "1_1") (pintype "passive"))
      (node (ref "C7") (pin "1") (pinfunction "1_1") (pintype "passive"))
      (node (ref "C8") (pin "2") (pinfunction "2_2") (pintype "passive"))
      (node (ref "C9") (pin "2") (pinfunction "2_2") (pintype "passive"))
      (node (ref "D1") (pin "1") (pinfunction "1_1") (pintype "passive"))
      (node (ref "D4") (pin "K") (pinfunction "K_K") (pintype "passive"))
      (node (ref "D5") (pin "K") (pinfunction "K_K") (pintype "passive"))
      (node (ref "D6") (pin "K") (pinfunction "K_K") (pintype "passive"))
      (node (ref "IC1") (pin "15") (pinfunction "GND_15") (pintype "passive"))
      (node (ref "IC2") (pin "25") (pinfunction "VSS_25") (pintype "passive"))
      (node (ref "J1") (pin "31") (pinfunction "31_31") (pintype "passive"))
      (node (ref "J1") (pin "32") (pinfunction "32_32") (pintype "passive"))
      (node (ref "J10") (pin "1") (pinfunction "1_1") (pintype "passive"))
      (node (ref "J14") (pin "1") (pinfunction "1_1") (pintype "passive"))
      (node (ref "J16") (pin "3") (pinfunction "3_3") (pintype "passive"))
      (node (ref "J17") (pin "3") (pinfunction "3_3") (pintype "passive"))
      (node (ref "J18") (pin "3") (pinfunction "3_3") (pintype "passive"))
      (node (ref "J19") (pin "3") (pinfunction "3_3") (pintype "passive"))
      (node (ref "J2") (pin "30") (pinfunction "30_30") (pintype "passive"))
      (node (ref "J2") (pin "31") (pinfunction "31_31") (pintype "passive"))
      (node (ref "J3") (pin "1") (pinfunction "1_1") (pintype "passive"))
      (node (ref "J4") (pin "1") (pinfunction "1_1") (pintype "passive"))
      (node (ref "J5") (pin "1") (pinfunction "1_1") (pintype "passive"))
      (node (ref "J6") (pin "1") (pinfunction "1_1") (pintype "passive"))
      (node (ref "J7") (pin "1") (pinfunction "1_1") (pintype "passive"))
      (node (ref "J8") (pin "5") (pinfunction "5_5") (pintype "passive"))
      (node (ref "J9") (pin "1") (pinfunction "1_1") (pintype "passive"))
      (node (ref "Q1") (pin "2") (pinfunction "E_2") (pintype "passive"))
      (node (ref "R20") (pin "1") (pinfunction "1_1") (pintype "passive"))
      (node (ref "R21") (pin "1") (pinfunction "1_1") (pintype "passive"))
      (node (ref "R23") (pin "2") (pinfunction "2_2") (pintype "passive"))
      (node (ref "R24") (pin "2") (pinfunction "2_2") (pintype "passive"))
      (node (ref "R4") (pin "1") (pinfunction "1_1") (pintype "passive"))
      (node (ref "R5") (pin "1") (pinfunction "1_1") (pintype "passive"))
      (node (ref "RJ1") (pin "7") (pinfunction "NC_7") (pintype "passive"))
      (node (ref "RJ1") (pin "8") (pinfunction "NC_8") (pintype "passive"))
      (node (ref "RJ1") (pin "MH1") (pinfunction "MH1_MH1") (pintype "passive"))
      (node (ref "RJ1") (pin "MH2") (pinfunction "MH2_MH2") (pintype "passive"))
      (node (ref "RJ1") (pin "MH3") (pinfunction "MH3_MH3") (pintype "passive"))
      (node (ref "RJ1") (pin "MH4") (pinfunction "MH4_MH4") (pintype "passive"))
      (node (ref "SW1") (pin "2") (pinfunction "2_2") (pintype "passive"))
      (node (ref "SW2") (pin "2") (pinfunction "2_2") (pintype "passive"))
      (node (ref "U1") (pin "8") (pinfunction "GND_8") (pintype "passive"))
      (node (ref "U2") (pin "2") (pinfunction "GND_2") (pintype "passive"))
      (node (ref "U2") (pin "8") (pinfunction "RS_8") (pintype "passive"))
      (node (ref "U3") (pin "2") (pinfunction "GND_2") (pintype "passive"))
      (node (ref "U3") (pin "8") (pinfunction "RS_8") (pintype "passive"))
      (node (ref "X1") (pin "2") (pinfunction "GND_2") (pintype "passive"))
    )
    (net (code "122") (name "Net-(BUZZER1--)") (class "Default")
      (node (ref "BUZZER1") (pin "2") (pinfunction "-_2") (pintype "passive"))
      (node (ref "Q1") (pin "3") (pinfunction "C_3") (pintype "passive"))
    )
    (net (code "123") (name "Net-(C8-Pad1)") (class "Default")
      (node (ref "C8") (pin "1") (pinfunction "1_1") (pintype "passive"))
      (node (ref "R6") (pin "2") (pinfunction "2_2") (pintype "passive"))
      (node (ref "R8") (pin "1") (pinfunction "1_1") (pintype "passive"))
    )
    (net (code "124") (name "Net-(C9-Pad1)") (class "Default")
      (node (ref "C9") (pin "1") (pinfunction "1_1") (pintype "passive"))
      (node (ref "R7") (pin "1") (pinfunction "1_1") (pintype "passive"))
      (node (ref "R9") (pin "2") (pinfunction "2_2") (pintype "passive"))
    )
    (net (code "125") (name "Net-(C11-Pad1)") (class "Default")
      (node (ref "C11") (pin "1") (pinfunction "1_1") (pintype "passive"))
      (node (ref "R10") (pin "2") (pinfunction "2_2") (pintype "passive"))
      (node (ref "R12") (pin "1") (pinfunction "1_1") (pintype "passive"))
    )
    (net (code "126") (name "Net-(C12-Pad1)") (class "Default")
      (node (ref "C12") (pin "1") (pinfunction "1_1") (pintype "passive"))
      (node (ref "R11") (pin "1") (pinfunction "1_1") (pintype "passive"))
      (node (ref "R13") (pin "2") (pinfunction "2_2") (pintype "passive"))
    )
    (net (code "127") (name "Net-(D1-Pad2)") (class "Default")
      (node (ref "D1") (pin "2") (pinfunction "2_2") (pintype "passive"))
      (node (ref "J8") (pin "MH1") (pinfunction "MH1_MH1") (pintype "passive"))
      (node (ref "J8") (pin "MH2") (pinfunction "MH2_MH2") (pintype "passive"))
      (node (ref "R4") (pin "2") (pinfunction "2_2") (pintype "passive"))
    )
    (net (code "128") (name "Net-(D4-PadA)") (class "Default")
      (node (ref "D4") (pin "A") (pinfunction "A_A") (pintype "passive"))
      (node (ref "R19") (pin "1") (pinfunction "1_1") (pintype "passive"))
    )
    (net (code "129") (name "Net-(D5-PadA)") (class "Default")
      (node (ref "D5") (pin "A") (pinfunction "A_A") (pintype "passive"))
      (node (ref "R22") (pin "1") (pinfunction "1_1") (pintype "passive"))
    )
    (net (code "130") (name "Net-(D6-PadA)") (class "Default")
      (node (ref "D6") (pin "A") (pinfunction "A_A") (pintype "passive"))
      (node (ref "R25") (pin "1") (pinfunction "1_1") (pintype "passive"))
    )
    (net (code "131") (name "Net-(IC1-C1+)") (class "Default")
      (node (ref "C4") (pin "2") (pinfunction "2_2") (pintype "passive"))
      (node (ref "IC1") (pin "1") (pinfunction "C1+_1") (pintype "passive"))
    )
    (net (code "132") (name "Net-(IC1-C1-)") (class "Default")
      (node (ref "C4") (pin "1") (pinfunction "1_1") (pintype "passive"))
      (node (ref "IC1") (pin "3") (pinfunction "C1-_3") (pintype "passive"))
    )
    (net (code "133") (name "Net-(IC1-C2+)") (class "Default")
      (node (ref "C5") (pin "2") (pinfunction "2_2") (pintype "passive"))
      (node (ref "IC1") (pin "4") (pinfunction "C2+_4") (pintype "passive"))
    )
    (net (code "134") (name "Net-(IC1-C2-)") (class "Default")
      (node (ref "C5") (pin "1") (pinfunction "1_1") (pintype "passive"))
      (node (ref "IC1") (pin "5") (pinfunction "C2-_5") (pintype "passive"))
    )
    (net (code "135") (name "Net-(IC1-V+)") (class "Default")
      (node (ref "C6") (pin "2") (pinfunction "2_2") (pintype "passive"))
      (node (ref "IC1") (pin "2") (pinfunction "V+_2") (pintype "passive"))
    )
    (net (code "136") (name "Net-(IC1-V-)") (class "Default")
      (node (ref "C7") (pin "2") (pinfunction "2_2") (pintype "passive"))
      (node (ref "IC1") (pin "6") (pinfunction "V-_6") (pintype "passive"))
    )
    (net (code "137") (name "Net-(IC2-MDIO)") (class "Default")
      (node (ref "IC2") (pin "12") (pinfunction "MDIO_12") (pintype "passive"))
      (node (ref "R18") (pin "1") (pinfunction "1_1") (pintype "passive"))
    )
    (net (code "138") (name "Net-(IC2-RBIAS)") (class "Default")
      (node (ref "IC2") (pin "24") (pinfunction "RBIAS_24") (pintype "passive"))
      (node (ref "R24") (pin "1") (pinfunction "1_1") (pintype "passive"))
    )
    (net (code "139") (name "Net-(IC2-RXN)") (class "Default")
      (node (ref "C23") (pin "2") (pinfunction "2_2") (pintype "passive"))
      (node (ref "IC2") (pin "22") (pinfunction "RXN_22") (pintype "passive"))
      (node (ref "R17") (pin "1") (pinfunction "1_1") (pintype "passive"))
      (node (ref "RJ1") (pin "6") (pinfunction "RD-_6") (pintype "passive"))
    )
    (net (code "140") (name "Net-(IC2-RXP)") (class "Default")
      (node (ref "C22") (pin "2") (pinfunction "2_2") (pintype "passive"))
      (node (ref "IC2") (pin "23") (pinfunction "RXP_23") (pintype "passive"))
      (node (ref "R16") (pin "1") (pinfunction "1_1") (pintype "passive"))
      (node (ref "RJ1") (pin "3") (pinfunction "RD+_3") (pintype "passive"))
    )
    (net (code "141") (name "Net-(IC2-TXN)") (class "Default")
      (node (ref "C21") (pin "2") (pinfunction "2_2") (pintype "passive"))
      (node (ref "IC2") (pin "20") (pinfunction "TXN_20") (pintype "passive"))
      (node (ref "R15") (pin "1") (pinfunction "1_1") (pintype "passive"))
      (node (ref "RJ1") (pin "2") (pinfunction "TD-_2") (pintype "passive"))
    )
    (net (code "142") (name "Net-(IC2-TXP)") (class "Default")
      (node (ref "C20") (pin "2") (pinfunction "2_2") (pintype "passive"))
      (node (ref "IC2") (pin "21") (pinfunction "TXP_21") (pintype "passive"))
      (node (ref "R14") (pin "1") (pinfunction "1_1") (pintype "passive"))
      (node (ref "RJ1") (pin "1") (pinfunction "TD+_1") (pintype "passive"))
    )
    (net (code "143") (name "Net-(IC2-XTAL1{slash}CLKIN)") (class "Default")
      (node (ref "IC2") (pin "5") (pinfunction "XTAL1/CLKIN_5") (pintype "passive"))
      (node (ref "X1") (pin "3") (pinfunction "OSC2_3") (pintype "passive"))
    )
    (net (code "144") (name "Net-(IC2-XTAL2)") (class "Default")
      (node (ref "IC2") (pin "4") (pinfunction "XTAL2_4") (pintype "passive"))
      (node (ref "X1") (pin "1") (pinfunction "OSC1_1") (pintype "passive"))
    )
    (net (code "145") (name "Net-(Q1-B)") (class "Default")
      (node (ref "Q1") (pin "1") (pinfunction "B_1") (pintype "passive"))
      (node (ref "R3") (pin "2") (pinfunction "2_2") (pintype "passive"))
      (node (ref "R5") (pin "2") (pinfunction "2_2") (pintype "passive"))
    )
    (net (code "146") (name "Net-(RJ1-LED(Y)_A)") (class "Default")
      (node (ref "R20") (pin "2") (pinfunction "2_2") (pintype "passive"))
      (node (ref "RJ1") (pin "12") (pinfunction "LED(Y)_A_12") (pintype "passive"))
    )
    (net (code "147") (name "Net-(RJ1-LED(Y)_K)") (class "Default")
      (node (ref "R21") (pin "2") (pinfunction "2_2") (pintype "passive"))
      (node (ref "RJ1") (pin "11") (pinfunction "LED(Y)_K_11") (pintype "passive"))
    )
    (net (code "148") (name "VCC_3V3") (class "Default")
      (node (ref "C18") (pin "2") (pinfunction "2_2") (pintype "passive"))
      (node (ref "IC2") (pin "9") (pinfunction "VDDIO_9") (pintype "passive"))
      (node (ref "J1") (pin "3") (pinfunction "3_3") (pintype "passive"))
      (node (ref "J1") (pin "4") (pinfunction "4_4") (pintype "passive"))
      (node (ref "L1") (pin "1") (pinfunction "1_1") (pintype "passive"))
    )
    (net (code "149") (name "VCC_3V3E") (class "Default")
      (node (ref "C19") (pin "2") (pinfunction "2_2") (pintype "passive"))
      (node (ref "C24") (pin "2") (pinfunction "2_2") (pintype "passive"))
      (node (ref "IC2") (pin "1") (pinfunction "VDD2A_1") (pintype "passive"))
      (node (ref "IC2") (pin "19") (pinfunction "VDD1A_19") (pintype "passive"))
      (node (ref "L1") (pin "2") (pinfunction "2_2") (pintype "passive"))
      (node (ref "R14") (pin "2") (pinfunction "2_2") (pintype "passive"))
      (node (ref "R15") (pin "2") (pinfunction "2_2") (pintype "passive"))
      (node (ref "R16") (pin "2") (pinfunction "2_2") (pintype "passive"))
      (node (ref "R17") (pin "2") (pinfunction "2_2") (pintype "passive"))
      (node (ref "RJ1") (pin "4") (pinfunction "TCT_4") (pintype "passive"))
      (node (ref "RJ1") (pin "5") (pinfunction "RCT_5") (pintype "passive"))
    )
    (net (code "150") (name "VCC_5V") (class "Default")
      (node (ref "C1") (pin "1") (pinfunction "1_1") (pintype "passive"))
      (node (ref "C10") (pin "2") (pinfunction "2_2") (pintype "passive"))
      (node (ref "C13") (pin "2") (pinfunction "2_2") (pintype "passive"))
      (node (ref "C2") (pin "1") (pinfunction "1_1") (pintype "passive"))
      (node (ref "C3") (pin "2") (pinfunction "2_2") (pintype "passive"))
      (node (ref "IC1") (pin "16") (pinfunction "VCC_16") (pintype "passive"))
      (node (ref "J1") (pin "1") (pinfunction "1_1") (pintype "passive"))
      (node (ref "J1") (pin "2") (pinfunction "2_2") (pintype "passive"))
      (node (ref "J10") (pin "4") (pinfunction "4_4") (pintype "passive"))
      (node (ref "J14") (pin "4") (pinfunction "4_4") (pintype "passive"))
      (node (ref "J3") (pin "4") (pinfunction "4_4") (pintype "passive"))
      (node (ref "J4") (pin "4") (pinfunction "4_4") (pintype "passive"))
      (node (ref "J5") (pin "4") (pinfunction "4_4") (pintype "passive"))
      (node (ref "J6") (pin "4") (pinfunction "4_4") (pintype "passive"))
      (node (ref "J7") (pin "4") (pinfunction "4_4") (pintype "passive"))
      (node (ref "J9") (pin "4") (pinfunction "4_4") (pintype "passive"))
      (node (ref "R1") (pin "2") (pinfunction "2_2") (pintype "passive"))
      (node (ref "R2") (pin "2") (pinfunction "2_2") (pintype "passive"))
      (node (ref "U1") (pin "1") (pinfunction "VCC_1") (pintype "passive"))
      (node (ref "U2") (pin "3") (pinfunction "VCC_3") (pintype "passive"))
      (node (ref "U3") (pin "3") (pinfunction "VCC_3") (pintype "passive"))
    )
    (net (code "151") (name "VCC_12V") (class "Default")
      (node (ref "BUZZER1") (pin "1") (pinfunction "+_1") (pintype "passive"))
      (node (ref "J16") (pin "1") (pinfunction "1_1") (pintype "passive"))
      (node (ref "J17") (pin "1") (pinfunction "1_1") (pintype "passive"))
      (node (ref "J18") (pin "1") (pinfunction "1_1") (pintype "passive"))
      (node (ref "J19") (pin "1") (pinfunction "1_1") (pintype "passive"))
    )
    (net (code "152") (name "unconnected-(IC1-R1IN-Pad13)") (class "Default")
      (node (ref "IC1") (pin "13") (pinfunction "R1IN_13") (pintype "passive+no_connect"))
    )
    (net (code "153") (name "unconnected-(IC1-R1OUT-Pad12)") (class "Default")
      (node (ref "IC1") (pin "12") (pinfunction "R1OUT_12") (pintype "passive+no_connect"))
    )
    (net (code "154") (name "unconnected-(IC1-T1IN-Pad11)") (class "Default")
      (node (ref "IC1") (pin "11") (pinfunction "T1IN_11") (pintype "passive+no_connect"))
    )
    (net (code "155") (name "unconnected-(IC1-T1OUT-Pad14)") (class "Default")
      (node (ref "IC1") (pin "14") (pinfunction "T1OUT_14") (pintype "passive+no_connect"))
    )
    (net (code "156") (name "unconnected-(IC2-RXER{slash}~{PHYAD0}-Pad10)") (class "Default")
      (node (ref "IC2") (pin "10") (pinfunction "RXER/~{PHYAD0}_10") (pintype "passive+no_connect"))
    )
    (net (code "157") (name "unconnected-(IC2-VDDCR-Pad6)") (class "Default")
      (node (ref "IC2") (pin "6") (pinfunction "VDDCR_6") (pintype "passive+no_connect"))
    )
    (net (code "158") (name "unconnected-(J8-Pad1)") (class "Default")
      (node (ref "J8") (pin "1") (pinfunction "1_1") (pintype "passive+no_connect"))
    )
    (net (code "159") (name "unconnected-(J8-Pad4)") (class "Default")
      (node (ref "J8") (pin "4") (pinfunction "4_4") (pintype "passive+no_connect"))
    )
    (net (code "160") (name "unconnected-(J8-Pad6)") (class "Default")
      (node (ref "J8") (pin "6") (pinfunction "6_6") (pintype "passive+no_connect"))
    )
    (net (code "161") (name "unconnected-(J8-Pad7)") (class "Default")
      (node (ref "J8") (pin "7") (pinfunction "7_7") (pintype "passive+no_connect"))
    )
    (net (code "162") (name "unconnected-(J8-Pad8)") (class "Default")
      (node (ref "J8") (pin "8") (pinfunction "8_8") (pintype "passive+no_connect"))
    )
    (net (code "163") (name "unconnected-(J8-Pad9)") (class "Default")
      (node (ref "J8") (pin "9") (pinfunction "9_9") (pintype "passive+no_connect"))
    )
    (net (code "164") (name "unconnected-(U1-D0-Pad2)") (class "Default")
      (node (ref "U1") (pin "2") (pinfunction "D0_2") (pintype "passive+no_connect"))
    )
    (net (code "165") (name "unconnected-(U1-D1-Pad3)") (class "Default")
      (node (ref "U1") (pin "3") (pinfunction "D1_3") (pintype "passive+no_connect"))
    )
    (net (code "166") (name "unconnected-(U1-D2-Pad4)") (class "Default")
      (node (ref "U1") (pin "4") (pinfunction "D2_4") (pintype "passive+no_connect"))
    )
    (net (code "167") (name "unconnected-(U1-D3-Pad5)") (class "Default")
      (node (ref "U1") (pin "5") (pinfunction "D3_5") (pintype "passive+no_connect"))
    )
    (net (code "168") (name "unconnected-(U1-D4-Pad6)") (class "Default")
      (node (ref "U1") (pin "6") (pinfunction "D4_6") (pintype "passive+no_connect"))
    )
    (net (code "169") (name "unconnected-(U1-D5-Pad7)") (class "Default")
      (node (ref "U1") (pin "7") (pinfunction "D5_7") (pintype "passive+no_connect"))
    )
    (net (code "170") (name "unconnected-(U1-RX-Pad13)") (class "Default")
      (node (ref "U1") (pin "13") (pinfunction "RX_13") (pintype "passive+no_connect"))
    )
    (net (code "171") (name "unconnected-(U1-SWCLK-Pad9)") (class "Default")
      (node (ref "U1") (pin "9") (pinfunction "SWCLK_9") (pintype "passive+no_connect"))
    )
    (net (code "172") (name "unconnected-(U1-SWDIO-Pad10)") (class "Default")
      (node (ref "U1") (pin "10") (pinfunction "SWDIO_10") (pintype "passive+no_connect"))
    )
    (net (code "173") (name "unconnected-(U1-TX-Pad14)") (class "Default")
      (node (ref "U1") (pin "14") (pinfunction "TX_14") (pintype "passive+no_connect"))
    )
    (net (code "174") (name "unconnected-(U2-Vref-Pad5)") (class "Default")
      (node (ref "U2") (pin "5") (pinfunction "Vref_5") (pintype "passive+no_connect"))
    )
    (net (code "175") (name "unconnected-(U3-Vref-Pad5)") (class "Default")
      (node (ref "U3") (pin "5") (pinfunction "Vref_5") (pintype "passive+no_connect"))
    )
  )
)
